# Micro.net
KiCad netlist of a schematic drawn in Altium Designer
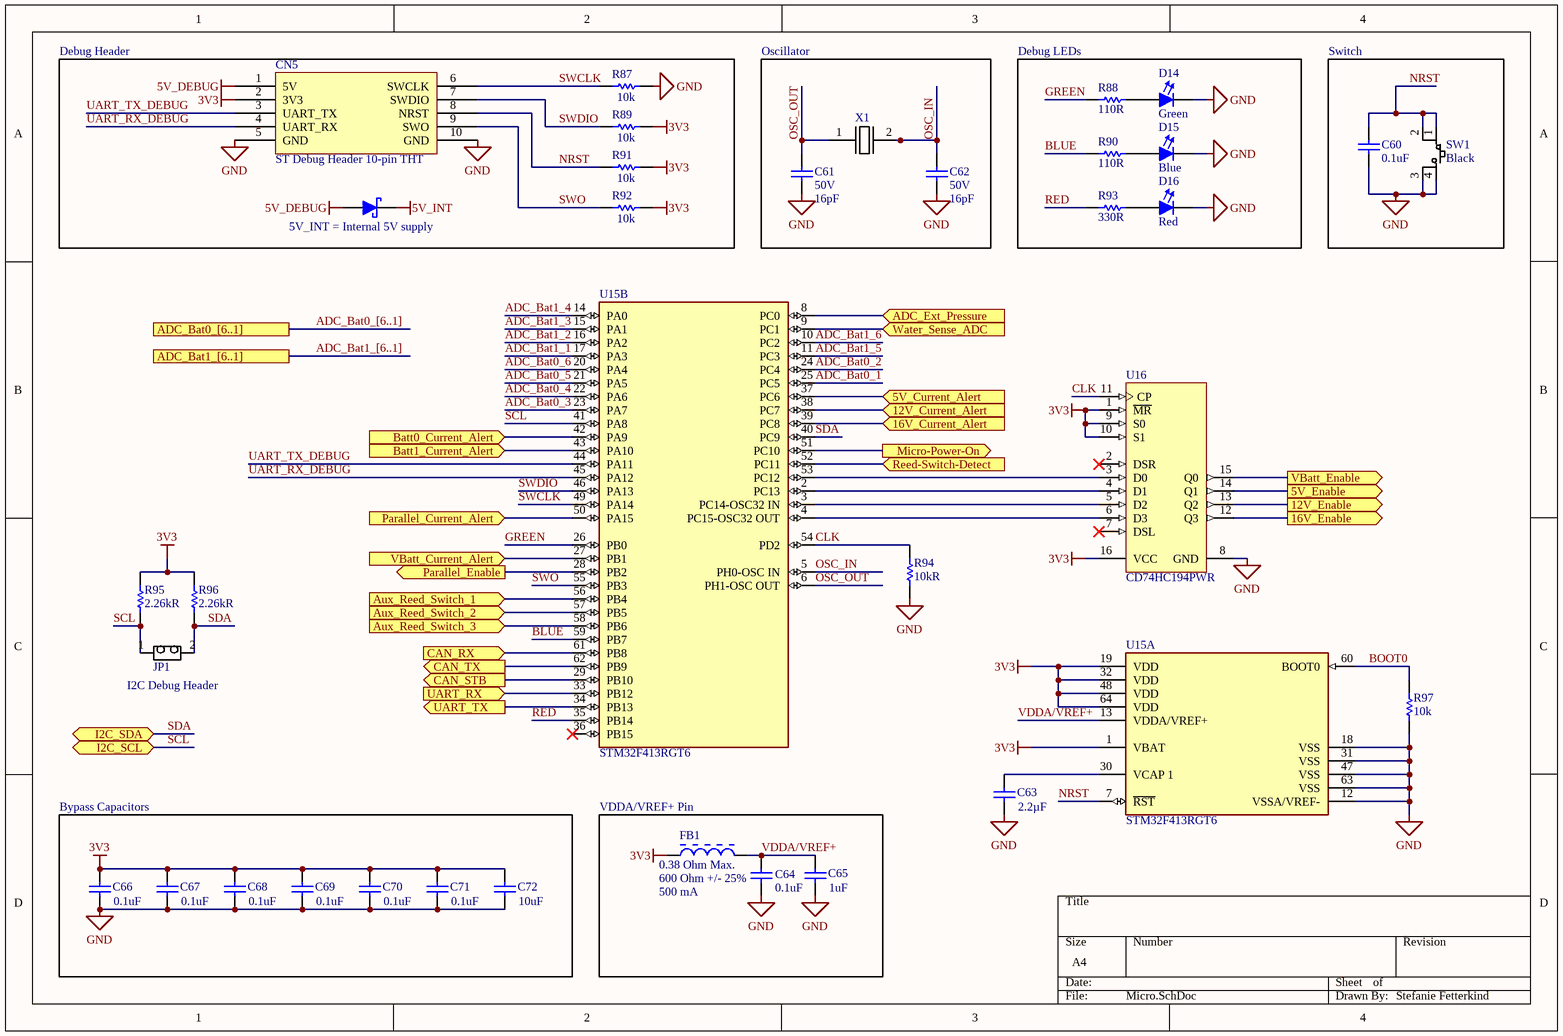
[diagram p0: Micro.SchDoc]

(export (version "E")
  (design (tool "Eeschema 10.0.6"))
  (components
    (comp (ref "C60")
      (value "CL10B104JB8NNNC")
      (footprint "FP-CL10-0_1-IPC_A")
      (description "CAP CER 0.1UF 50V X7R 0603")
      (fields
        (field (name "TOLERANCE") "5%")
        (field (name "VOLTAGE") "50V")
        (field (name "CAPACITANCE") "0.1uF")
      )
      (libsource (lib "AUVIC") (part "CAP-NP-2"))
    )
    (comp (ref "C61")
      (value "16pF Ceramic 50V 5% 0603")
      (footprint "CAPC1608X90X35LL10T15")
      (description "Cap Ceramic 16pF 50V C0G 5% SMD 0603 125C Paper T/R")
      (fields
        (field (name "VOLTAGE") "50V")
        (field (name "TOLERANCE") "5%")
        (field (name "CAPACITANCE") "16pF")
      )
      (libsource (lib "AUVIC") (part "CAP"))
    )
    (comp (ref "C62")
      (value "16pF Ceramic 50V 5% 0603")
      (footprint "CAPC1608X90X35LL10T15")
      (description "Cap Ceramic 16pF 50V C0G 5% SMD 0603 125C Paper T/R")
      (fields
        (field (name "VOLTAGE") "50V")
        (field (name "TOLERANCE") "5%")
        (field (name "CAPACITANCE") "16pF")
      )
      (libsource (lib "AUVIC") (part "CAP"))
    )
    (comp (ref "C63")
      (value "2.2µF")
      (footprint "CAPC1608N(0603\")")
      (description "Capacitor, Ceramic, 50V, 10%, 0603 SMD, X5R")
      (fields
        (field (name "Comment") "2.2uF, 50V, 0603 SMD, X5R, Ceramic")
        (field (name "MADE BY") "*")
        (field (name "PUBLISHER") "AUVic")
      )
      (libsource (lib "AUVIC") (part "Symbol"))
    )
    (comp (ref "C64")
      (value "CL10B104JB8NNNC")
      (footprint "FP-CL10-0_1-IPC_A")
      (description "CAP CER 0.1UF 50V X7R 0603")
      (fields
        (field (name "CAPACITANCE") "0.1uF")
        (field (name "VOLTAGE") "50V")
        (field (name "TOLERANCE") "5%")
      )
      (libsource (lib "AUVIC") (part "CAP-NP-2"))
    )
    (comp (ref "C65")
      (value "CL21B105KBFNNNG")
      (footprint "0803 CAP")
      (description "SAMSUNG ELECTRO-MECHANICS - CL21B105KBFNNNG - MLCC CAPACITORS")
      (fields
        (field (name "TOLERANCE") "10%")
        (field (name "CAPACITANCE") "1uF")
        (field (name "VOLTAGE") "50V")
      )
      (libsource (lib "") (part "Symbol_1"))
    )
    (comp (ref "C66")
      (value "CL10B104JB8NNNC")
      (footprint "FP-CL10-0_1-IPC_A")
      (description "CAP CER 0.1UF 50V X7R 0603")
      (fields
        (field (name "CAPACITANCE") "0.1uF")
        (field (name "VOLTAGE") "50V")
        (field (name "TOLERANCE") "5%")
      )
      (libsource (lib "AUVIC") (part "CAP-NP-2"))
    )
    (comp (ref "C67")
      (value "CL10B104JB8NNNC")
      (footprint "FP-CL10-0_1-IPC_A")
      (description "CAP CER 0.1UF 50V X7R 0603")
      (fields
        (field (name "CAPACITANCE") "0.1uF")
        (field (name "VOLTAGE") "50V")
        (field (name "TOLERANCE") "5%")
      )
      (libsource (lib "AUVIC") (part "CAP-NP-2"))
    )
    (comp (ref "C68")
      (value "CL10B104JB8NNNC")
      (footprint "FP-CL10-0_1-IPC_A")
      (description "CAP CER 0.1UF 50V X7R 0603")
      (fields
        (field (name "CAPACITANCE") "0.1uF")
        (field (name "VOLTAGE") "50V")
        (field (name "TOLERANCE") "5%")
      )
      (libsource (lib "AUVIC") (part "CAP-NP-2"))
    )
    (comp (ref "C69")
      (value "CL10B104JB8NNNC")
      (footprint "FP-CL10-0_1-IPC_A")
      (description "CAP CER 0.1UF 50V X7R 0603")
      (fields
        (field (name "CAPACITANCE") "0.1uF")
        (field (name "VOLTAGE") "50V")
        (field (name "TOLERANCE") "5%")
      )
      (libsource (lib "AUVIC") (part "CAP-NP-2"))
    )
    (comp (ref "C70")
      (value "CL10B104JB8NNNC")
      (footprint "FP-CL10-0_1-IPC_A")
      (description "CAP CER 0.1UF 50V X7R 0603")
      (fields
        (field (name "CAPACITANCE") "0.1uF")
        (field (name "VOLTAGE") "50V")
        (field (name "TOLERANCE") "5%")
      )
      (libsource (lib "AUVIC") (part "CAP-NP-2"))
    )
    (comp (ref "C71")
      (value "CL10B104JB8NNNC")
      (footprint "FP-CL10-0_1-IPC_A")
      (description "CAP CER 0.1UF 50V X7R 0603")
      (fields
        (field (name "CAPACITANCE") "0.1uF")
        (field (name "VOLTAGE") "50V")
        (field (name "TOLERANCE") "5%")
      )
      (libsource (lib "AUVIC") (part "CAP-NP-2"))
    )
    (comp (ref "C72")
      (value "CL31B106KBHNNNE")
      (footprint "CAPC3216X180X50ML20T30")
      (description "Cap Ceramic 10uF 50V X7R 10% Pad SMD 1206 125°C T/R")
      (fields (field (name "CAPACITANCE") "10uF") (field (name "TOLERANCE") "10%"))
      (libsource (lib "AUVIC") (part "CAP-NP-2"))
    )
    (comp (ref "CN5")
      (value "ST Debug Header 10-pin THT")
      (footprint "10-pin shrouded header THT")
      (description "CONN HEADER VERT 10POS 2.54MM")
      (libsource (lib "AUVIC") (part "ST Debug Header 10-pin"))
    )
    (comp (ref "D14")
      (value "LT Q39G-Q1OO-25-1")
      (footprint "FP-LB_Q39E-MFG")
      (description "LED GREEN DIFFUSED 0603 SMD")
      (fields (field (name "COLOR") "Green"))
      (libsource (lib "") (part "Symbol_3"))
    )
    (comp (ref "D15")
      (value "LBQ39E-N1OO-35-1")
      (footprint "FP-LB_Q39E-MFG")
      (description "LED BLUE DIFFUSED 0603 SMD")
      (fields (field (name "COLOR") "Blue"))
      (libsource (lib "") (part "Symbol_3"))
    )
    (comp (ref "D16")
      (value "LSQ976-NR-1")
      (footprint "FP-LB_Q39E-MFG")
      (description "LED Red 645nm 2-Pin Chip 0603(1608Metric) T/R")
      (fields (field (name "COLOR") "Red"))
      (libsource (lib "") (part "Symbol_3"))
    )
    (comp (ref "D17")
      (value "CUS08F30,H3F")
      (footprint "SC-76")
      (description "Diode Schottky 30V 800mA Surface Mount USC")
      (libsource (lib "") (part "Symbol_5"))
    )
    (comp (ref "FB1")
      (value "BLM18AG601SN1D")
      (footprint "MURA-BLM18-F-H1-CHIP-2_V")
      (fields
        (field (name "MANUFACTURER") "Murata")
        (field (name "DC RESISTANCE") "0.38 Ohm Max.")
        (field (name "IMPEDANCE (AT 100 MHZ)") "600 Ohm +/- 25%")
        (field (name "RATED CURRENT") "500 mA")
      )
      (libsource (lib "Altium Content Vault") (part "MURA-FB-2"))
    )
    (comp (ref "JP1")
      (value "1x2 Male Header")
      (footprint "2X1 Males Header")
      (fields (field (name "MADE BY") "Andy Bates"))
      (libsource (lib "AUVIC") (part "1x2 Male Header"))
    )
    (comp (ref "R87")
      (value "10k")
      (footprint "RESC1608N(0603\")")
      (description "10kR, 1%, 1/10W, 0603 SMD")
      (fields (field (name "MADE BY") "Ashwin Sira"))
      (libsource (lib "") (part "Symbol_4"))
    )
    (comp (ref "R88")
      (value "RC0603FR-07110RL")
      (footprint "RESC1608X55X25ML10T15")
      (description "RES SMD 110 OHM 1% 1/10W 0603")
      (fields (field (name "TOLERANCE") "1%") (field (name "RESISTANCE") "110R"))
      (libsource (lib "AUVIC") (part "RES"))
    )
    (comp (ref "R89")
      (value "10k")
      (footprint "RESC1608N(0603\")")
      (description "10kR, 1%, 1/10W, 0603 SMD")
      (fields (field (name "MADE BY") "Ashwin Sira"))
      (libsource (lib "") (part "Symbol_4"))
    )
    (comp (ref "R90")
      (value "RC0603FR-07110RL")
      (footprint "RESC1608X55X25ML10T15")
      (description "RES SMD 110 OHM 1% 1/10W 0603")
      (fields (field (name "TOLERANCE") "1%") (field (name "RESISTANCE") "110R"))
      (libsource (lib "AUVIC") (part "RES"))
    )
    (comp (ref "R91")
      (value "10k")
      (footprint "RESC1608N(0603\")")
      (description "10kR, 1%, 1/10W, 0603 SMD")
      (fields (field (name "MADE BY") "Ashwin Sira"))
      (libsource (lib "") (part "Symbol_4"))
    )
    (comp (ref "R92")
      (value "10k")
      (footprint "RESC1608N(0603\")")
      (description "10kR, 1%, 1/10W, 0603 SMD")
      (fields (field (name "MADE BY") "Ashwin Sira"))
      (libsource (lib "") (part "Symbol_4"))
    )
    (comp (ref "R93")
      (value "CRCW0603330RFKEA")
      (footprint "FP-CRCW0603-e3-IPC_A")
      (description "Res Thick Film 0603 330 Ohm 1% 0.1W(1/10W) +/-100ppm/ßC Pad SMD Automotive T/R")
      (fields (field (name "RESISTANCE") "330R") (field (name "TOLERANCE") "1%"))
      (libsource (lib "AUVIC") (part "RES"))
    )
    (comp (ref "R94")
      (value "RC0603FR-0710KL")
      (footprint "RESC1608X55X25ML10T15")
      (description "Res General Purpose Thick Film 0603 10K Ohm 1% 1/10W ±100ppm/°C Molded SMD Paper T/R")
      (fields (field (name "RESISTANCE") "10kR") (field (name "TOLERANCE") "1%"))
      (libsource (lib "AUVIC") (part "RES-2"))
    )
    (comp (ref "R95")
      (value "RC0603FR-072K26L")
      (footprint "RESC0603(1608)_M")
      (description "RES SMD 2.26K OHM 1% 1/10W 0603")
      (fields (field (name "TOLERANCE") "1%") (field (name "RESISTANCE") "2.26kR"))
      (libsource (lib "AUVIC") (part "RES"))
    )
    (comp (ref "R96")
      (value "RC0603FR-072K26L")
      (footprint "RESC0603(1608)_M")
      (description "RES SMD 2.26K OHM 1% 1/10W 0603")
      (fields (field (name "TOLERANCE") "1%") (field (name "RESISTANCE") "2.26kR"))
      (libsource (lib "AUVIC") (part "RES"))
    )
    (comp (ref "R97")
      (value "10k")
      (footprint "RESC1608N(0603\")")
      (description "10kR, 1%, 1/10W, 0603 SMD")
      (fields (field (name "MADE BY") "Ashwin Sira"))
      (libsource (lib "") (part "Symbol_4"))
    )
    (comp (ref "SW1")
      (value "PTS645SL43SMTR92LFS")
      (footprint "4-SPST-NO")
      (description "Black Switch Tactile N.O. SPST Round Button Gull Wing 0.05A 12VDC 100000Cycles 1.27N SMD T/R")
      (fields (field (name "BUTTON COLOUR") "Black"))
      (libsource (lib "") (part "Symbol_6"))
    )
    (comp (ref "U15")
      (value "STM32F413RGT6")
      (footprint "FP-LQFP64-5W-IPC_A")
      (description "STMICROELECTRONICS - STM32F413RGT6 - MCU, ARM CORTEX-M4, 100MHZ, LQFP-64")
      (libsource (lib "AUVIC") (part "7f3deadac312a1e532344b4e443717e"))
    )
    (comp (ref "U16")
      (value "CD74HC194PWR")
      (footprint "PW0016A_M")
      (description "IC SHFT REGSTR UNIV BIDIR16TSSOP")
      (libsource (lib "AUVIC") (part "TI-CD74HCX194-16"))
    )
    (comp (ref "X1")
      (value "Oscillator 8MHz 40ESR")
      (footprint "HC49/US")
      (description "8Mhz 40ESR  16pF -20°C ~ 70°C")
      (fields (field (name "MADE BY") "Lyden Smith"))
      (libsource (lib "") (part "Symbol_2"))
    )
  )
  (nets
    (net (code "1") (name "/5V_Current_Alert") (class "Default")
      (node (ref "U15") (pin "37") (pinfunction "PC6_37") (pintype "bidirectional"))
    )
    (net (code "2") (name "/5V_Enable") (class "Default")
      (node (ref "U16") (pin "14") (pinfunction "Q1_14") (pintype "output"))
    )
    (net (code "3") (name "/12V_Current_Alert") (class "Default")
      (node (ref "U15") (pin "38") (pinfunction "PC7_38") (pintype "bidirectional"))
    )
    (net (code "4") (name "/12V_Enable") (class "Default")
      (node (ref "U16") (pin "13") (pinfunction "Q2_13") (pintype "output"))
    )
    (net (code "5") (name "/16V_Current_Alert") (class "Default")
      (node (ref "U15") (pin "39") (pinfunction "PC8_39") (pintype "bidirectional"))
    )
    (net (code "6") (name "/16V_Enable") (class "Default")
      (node (ref "U16") (pin "12") (pinfunction "Q3_12") (pintype "output"))
    )
    (net (code "7") (name "/ADC_Bat0_1") (class "Default")
      (node (ref "U15") (pin "25") (pinfunction "PC5_25") (pintype "bidirectional"))
    )
    (net (code "8") (name "/ADC_Bat0_2") (class "Default")
      (node (ref "U15") (pin "24") (pinfunction "PC4_24") (pintype "bidirectional"))
    )
    (net (code "9") (name "/ADC_Bat0_3") (class "Default")
      (node (ref "U15") (pin "23") (pinfunction "PA7_23") (pintype "bidirectional"))
    )
    (net (code "10") (name "/ADC_Bat0_4") (class "Default")
      (node (ref "U15") (pin "22") (pinfunction "PA6_22") (pintype "bidirectional"))
    )
    (net (code "11") (name "/ADC_Bat0_5") (class "Default")
      (node (ref "U15") (pin "21") (pinfunction "PA5_21") (pintype "bidirectional"))
    )
    (net (code "12") (name "/ADC_Bat0_6") (class "Default")
      (node (ref "U15") (pin "20") (pinfunction "PA4_20") (pintype "bidirectional"))
    )
    (net (code "14") (name "/ADC_Bat1_1") (class "Default")
      (node (ref "U15") (pin "17") (pinfunction "PA3_17") (pintype "bidirectional"))
    )
    (net (code "15") (name "/ADC_Bat1_2") (class "Default")
      (node (ref "U15") (pin "16") (pinfunction "PA2_16") (pintype "bidirectional"))
    )
    (net (code "16") (name "/ADC_Bat1_3") (class "Default")
      (node (ref "U15") (pin "15") (pinfunction "PA1_15") (pintype "bidirectional"))
    )
    (net (code "17") (name "/ADC_Bat1_4") (class "Default")
      (node (ref "U15") (pin "14") (pinfunction "PA0_14") (pintype "bidirectional"))
    )
    (net (code "18") (name "/ADC_Bat1_5") (class "Default")
      (node (ref "U15") (pin "11") (pinfunction "PC3_11") (pintype "bidirectional"))
    )
    (net (code "19") (name "/ADC_Bat1_6") (class "Default")
      (node (ref "U15") (pin "10") (pinfunction "PC2_10") (pintype "bidirectional"))
    )
    (net (code "21") (name "/ADC_Ext_Pressure") (class "Default")
      (node (ref "U15") (pin "8") (pinfunction "PC0_8") (pintype "bidirectional"))
    )
    (net (code "22") (name "/Aux_Reed_Switch_1") (class "Default")
      (node (ref "U15") (pin "56") (pinfunction "PB4_56") (pintype "bidirectional"))
    )
    (net (code "23") (name "/Aux_Reed_Switch_2") (class "Default")
      (node (ref "U15") (pin "57") (pinfunction "PB5_57") (pintype "bidirectional"))
    )
    (net (code "24") (name "/Aux_Reed_Switch_3") (class "Default")
      (node (ref "U15") (pin "58") (pinfunction "PB6_58") (pintype "bidirectional"))
    )
    (net (code "25") (name "/BLUE") (class "Default")
      (node (ref "R90") (pin "2") (pinfunction "2_2") (pintype "passive"))
      (node (ref "U15") (pin "59") (pinfunction "PB7_59") (pintype "bidirectional"))
    )
    (net (code "26") (name "/BOOT0") (class "Default")
      (node (ref "R97") (pin "2") (pinfunction "2_2") (pintype "passive"))
      (node (ref "U15") (pin "60") (pinfunction "BOOT0_60") (pintype "input"))
    )
    (net (code "27") (name "/Batt0_Current_Alert") (class "Default")
      (node (ref "U15") (pin "42") (pinfunction "PA9_42") (pintype "bidirectional"))
    )
    (net (code "28") (name "/Batt1_Current_Alert") (class "Default")
      (node (ref "U15") (pin "43") (pinfunction "PA10_43") (pintype "bidirectional"))
    )
    (net (code "29") (name "/CAN_RX") (class "Default")
      (node (ref "U15") (pin "61") (pinfunction "PB8_61") (pintype "bidirectional"))
    )
    (net (code "30") (name "/CAN_STB") (class "Default")
      (node (ref "U15") (pin "29") (pinfunction "PB10_29") (pintype "bidirectional"))
    )
    (net (code "31") (name "/CAN_TX") (class "Default")
      (node (ref "U15") (pin "62") (pinfunction "PB9_62") (pintype "bidirectional"))
    )
    (net (code "32") (name "/CLK") (class "Default")
      (node (ref "R94") (pin "1") (pinfunction "1_1") (pintype "passive"))
      (node (ref "U15") (pin "54") (pinfunction "PD2_54") (pintype "bidirectional"))
      (node (ref "U16") (pin "11") (pinfunction "CP_11") (pintype "input"))
    )
    (net (code "33") (name "/GREEN") (class "Default")
      (node (ref "R88") (pin "2") (pinfunction "2_2") (pintype "passive"))
      (node (ref "U15") (pin "26") (pinfunction "PB0_26") (pintype "bidirectional"))
    )
    (net (code "34") (name "/Micro-Power-On") (class "Default")
      (node (ref "U15") (pin "51") (pinfunction "PC10_51") (pintype "bidirectional"))
    )
    (net (code "35") (name "/NRST") (class "Default")
      (node (ref "C60") (pin "1") (pinfunction "1_1") (pintype "passive"))
      (node (ref "CN5") (pin "8") (pinfunction "NRST_8") (pintype "passive"))
      (node (ref "R91") (pin "1") (pinfunction "1_1") (pintype "passive"))
      (node (ref "SW1") (pin "1") (pinfunction "1_1") (pintype "passive"))
      (node (ref "SW1") (pin "2") (pinfunction "2_2") (pintype "passive"))
      (node (ref "U15") (pin "7") (pinfunction "~{RST}_7") (pintype "bidirectional"))
    )
    (net (code "36") (name "/OSC_IN") (class "Default")
      (node (ref "C62") (pin "2") (pinfunction "2_2") (pintype "passive"))
      (node (ref "U15") (pin "5") (pinfunction "PH0-OSC_IN_5") (pintype "bidirectional"))
      (node (ref "X1") (pin "2") (pinfunction "2_2") (pintype "passive"))
    )
    (net (code "37") (name "/OSC_OUT") (class "Default")
      (node (ref "C61") (pin "2") (pinfunction "2_2") (pintype "passive"))
      (node (ref "U15") (pin "6") (pinfunction "PH1-OSC_OUT_6") (pintype "bidirectional"))
      (node (ref "X1") (pin "1") (pinfunction "1_1") (pintype "passive"))
    )
    (net (code "38") (name "/Parallel_Current_Alert") (class "Default")
      (node (ref "U15") (pin "50") (pinfunction "PA15_50") (pintype "bidirectional"))
    )
    (net (code "39") (name "/Parallel_Enable") (class "Default")
      (node (ref "U15") (pin "28") (pinfunction "PB2_28") (pintype "bidirectional"))
    )
    (net (code "40") (name "/RED") (class "Default")
      (node (ref "R93") (pin "1") (pinfunction "1_1") (pintype "passive"))
      (node (ref "U15") (pin "35") (pinfunction "PB14_35") (pintype "bidirectional"))
    )
    (net (code "41") (name "/Reed-Switch-Detect") (class "Default")
      (node (ref "U15") (pin "52") (pinfunction "PC11_52") (pintype "bidirectional"))
    )
    (net (code "42") (name "/SCL") (class "Default")
      (node (ref "JP1") (pin "1") (pinfunction "1_1") (pintype "passive"))
      (node (ref "R95") (pin "1") (pinfunction "1_1") (pintype "passive"))
      (node (ref "U15") (pin "41") (pinfunction "PA8_41") (pintype "bidirectional"))
    )
    (net (code "43") (name "/SDA") (class "Default")
      (node (ref "JP1") (pin "2") (pinfunction "2_2") (pintype "passive"))
      (node (ref "R96") (pin "1") (pinfunction "1_1") (pintype "passive"))
      (node (ref "U15") (pin "40") (pinfunction "PC9_40") (pintype "bidirectional"))
    )
    (net (code "44") (name "/SWCLK") (class "Default")
      (node (ref "CN5") (pin "6") (pinfunction "SWCLK_6") (pintype "passive"))
      (node (ref "R87") (pin "1") (pinfunction "1_1") (pintype "passive"))
      (node (ref "U15") (pin "49") (pinfunction "PA14_49") (pintype "bidirectional"))
    )
    (net (code "45") (name "/SWDIO") (class "Default")
      (node (ref "CN5") (pin "7") (pinfunction "SWDIO_7") (pintype "passive"))
      (node (ref "R89") (pin "1") (pinfunction "1_1") (pintype "passive"))
      (node (ref "U15") (pin "46") (pinfunction "PA13_46") (pintype "bidirectional"))
    )
    (net (code "46") (name "/SWO") (class "Default")
      (node (ref "CN5") (pin "9") (pinfunction "SWO_9") (pintype "passive"))
      (node (ref "R92") (pin "1") (pinfunction "1_1") (pintype "passive"))
      (node (ref "U15") (pin "55") (pinfunction "PB3_55") (pintype "bidirectional"))
    )
    (net (code "47") (name "/UART_RX") (class "Default")
      (node (ref "U15") (pin "33") (pinfunction "PB12_33") (pintype "bidirectional"))
    )
    (net (code "48") (name "/UART_RX_DEBUG") (class "Default")
      (node (ref "CN5") (pin "4") (pinfunction "UART_RX_4") (pintype "passive"))
      (node (ref "U15") (pin "45") (pinfunction "PA12_45") (pintype "bidirectional"))
    )
    (net (code "49") (name "/UART_TX") (class "Default")
      (node (ref "U15") (pin "34") (pinfunction "PB13_34") (pintype "bidirectional"))
    )
    (net (code "50") (name "/UART_TX_DEBUG") (class "Default")
      (node (ref "CN5") (pin "3") (pinfunction "UART_TX_3") (pintype "passive"))
      (node (ref "U15") (pin "44") (pinfunction "PA11_44") (pintype "bidirectional"))
    )
    (net (code "51") (name "/VBatt_Current_Alert") (class "Default")
      (node (ref "U15") (pin "27") (pinfunction "PB1_27") (pintype "bidirectional"))
    )
    (net (code "52") (name "/VBatt_Enable") (class "Default")
      (node (ref "U16") (pin "15") (pinfunction "Q0_15") (pintype "output"))
    )
    (net (code "53") (name "/VDDA{slash}VREF+") (class "Default")
      (node (ref "C64") (pin "1") (pinfunction "1_1") (pintype "passive"))
      (node (ref "C65") (pin "2") (pinfunction "2_2") (pintype "passive"))
      (node (ref "FB1") (pin "2") (pinfunction "2_2") (pintype "passive"))
      (node (ref "U15") (pin "13") (pinfunction "VDDA/VREF+_13") (pintype "power_in"))
    )
    (net (code "54") (name "/Water_Sense_ADC") (class "Default")
      (node (ref "U15") (pin "9") (pinfunction "PC1_9") (pintype "bidirectional"))
    )
    (net (code "55") (name "3V3") (class "Default")
      (node (ref "C66") (pin "1") (pinfunction "1_1") (pintype "passive"))
      (node (ref "C67") (pin "1") (pinfunction "1_1") (pintype "passive"))
      (node (ref "C68") (pin "1") (pinfunction "1_1") (pintype "passive"))
      (node (ref "C69") (pin "1") (pinfunction "1_1") (pintype "passive"))
      (node (ref "C70") (pin "1") (pinfunction "1_1") (pintype "passive"))
      (node (ref "C71") (pin "1") (pinfunction "1_1") (pintype "passive"))
      (node (ref "C72") (pin "2") (pinfunction "2_2") (pintype "passive"))
      (node (ref "CN5") (pin "2") (pinfunction "3V3_2") (pintype "passive"))
      (node (ref "FB1") (pin "1") (pinfunction "1_1") (pintype "passive"))
      (node (ref "R89") (pin "2") (pinfunction "2_2") (pintype "passive"))
      (node (ref "R91") (pin "2") (pinfunction "2_2") (pintype "passive"))
      (node (ref "R92") (pin "2") (pinfunction "2_2") (pintype "passive"))
      (node (ref "R95") (pin "2") (pinfunction "2_2") (pintype "passive"))
      (node (ref "R96") (pin "2") (pinfunction "2_2") (pintype "passive"))
      (node (ref "U15") (pin "1") (pinfunction "VBAT_1") (pintype "power_in"))
      (node (ref "U15") (pin "19") (pinfunction "VDD_19") (pintype "power_in"))
      (node (ref "U15") (pin "32") (pinfunction "VDD_32") (pintype "power_in"))
      (node (ref "U15") (pin "48") (pinfunction "VDD_48") (pintype "power_in"))
      (node (ref "U15") (pin "64") (pinfunction "VDD_64") (pintype "power_in"))
      (node (ref "U16") (pin "1") (pinfunction "~{MR}_1") (pintype "input"))
      (node (ref "U16") (pin "10") (pinfunction "S1_10") (pintype "input"))
      (node (ref "U16") (pin "16") (pinfunction "VCC_16") (pintype "power_in"))
      (node (ref "U16") (pin "9") (pinfunction "S0_9") (pintype "input"))
    )
    (net (code "56") (name "5V_DEBUG") (class "Default")
      (node (ref "CN5") (pin "1") (pinfunction "5V_1") (pintype "passive"))
      (node (ref "D17") (pin "A") (pinfunction "Anode_A") (pintype "passive"))
    )
    (net (code "57") (name "5V_INT") (class "Default")
      (node (ref "D17") (pin "K") (pinfunction "Cathode_K") (pintype "passive"))
    )
    (net (code "58") (name "GND") (class "Default")
      (node (ref "C60") (pin "2") (pinfunction "2_2") (pintype "passive"))
      (node (ref "C61") (pin "1") (pinfunction "1_1") (pintype "passive"))
      (node (ref "C62") (pin "1") (pinfunction "1_1") (pintype "passive"))
      (node (ref "C63") (pin "1") (pinfunction "Anode_1") (pintype "passive"))
      (node (ref "C64") (pin "2") (pinfunction "2_2") (pintype "passive"))
      (node (ref "C65") (pin "1") (pinfunction "1_1") (pintype "passive"))
      (node (ref "C66") (pin "2") (pinfunction "2_2") (pintype "passive"))
      (node (ref "C67") (pin "2") (pinfunction "2_2") (pintype "passive"))
      (node (ref "C68") (pin "2") (pinfunction "2_2") (pintype "passive"))
      (node (ref "C69") (pin "2") (pinfunction "2_2") (pintype "passive"))
      (node (ref "C70") (pin "2") (pinfunction "2_2") (pintype "passive"))
      (node (ref "C71") (pin "2") (pinfunction "2_2") (pintype "passive"))
      (node (ref "C72") (pin "1") (pinfunction "1_1") (pintype "passive"))
      (node (ref "CN5") (pin "10") (pinfunction "GND_10") (pintype "passive"))
      (node (ref "CN5") (pin "5") (pinfunction "GND_5") (pintype "passive"))
      (node (ref "D14") (pin "1") (pinfunction "Cathode_1") (pintype "passive"))
      (node (ref "D15") (pin "1") (pinfunction "Cathode_1") (pintype "passive"))
      (node (ref "D16") (pin "1") (pinfunction "Cathode_1") (pintype "passive"))
      (node (ref "R87") (pin "2") (pinfunction "2_2") (pintype "passive"))
      (node (ref "R94") (pin "2") (pinfunction "2_2") (pintype "passive"))
      (node (ref "R97") (pin "1") (pinfunction "1_1") (pintype "passive"))
      (node (ref "SW1") (pin "3") (pinfunction "3_3") (pintype "passive"))
      (node (ref "SW1") (pin "4") (pinfunction "4_4") (pintype "passive"))
      (node (ref "U15") (pin "12") (pinfunction "VSSA/VREF-_12") (pintype "power_in"))
      (node (ref "U15") (pin "18") (pinfunction "VSS_18") (pintype "power_in"))
      (node (ref "U15") (pin "31") (pinfunction "VSS_31") (pintype "power_in"))
      (node (ref "U15") (pin "47") (pinfunction "VSS_47") (pintype "power_in"))
      (node (ref "U15") (pin "63") (pinfunction "VSS_63") (pintype "power_in"))
      (node (ref "U16") (pin "8") (pinfunction "GND_8") (pintype "power_in"))
    )
    (net (code "59") (name "Net-(C63-Cathode)") (class "Default")
      (node (ref "C63") (pin "2") (pinfunction "Cathode_2") (pintype "passive"))
      (node (ref "U15") (pin "30") (pinfunction "VCAP_1_30") (pintype "power_in"))
    )
    (net (code "60") (name "Net-(D14-Anode)") (class "Default")
      (node (ref "D14") (pin "2") (pinfunction "Anode_2") (pintype "passive"))
      (node (ref "R88") (pin "1") (pinfunction "1_1") (pintype "passive"))
    )
    (net (code "61") (name "Net-(D15-Anode)") (class "Default")
      (node (ref "D15") (pin "2") (pinfunction "Anode_2") (pintype "passive"))
      (node (ref "R90") (pin "1") (pinfunction "1_1") (pintype "passive"))
    )
    (net (code "62") (name "Net-(D16-Anode)") (class "Default")
      (node (ref "D16") (pin "2") (pinfunction "Anode_2") (pintype "passive"))
      (node (ref "R93") (pin "2") (pinfunction "2_2") (pintype "passive"))
    )
    (net (code "63") (name "Net-(U15B-PC12)") (class "Default")
      (node (ref "U15") (pin "53") (pinfunction "PC12_53") (pintype "bidirectional"))
      (node (ref "U16") (pin "3") (pinfunction "D0_3") (pintype "input"))
    )
    (net (code "64") (name "Net-(U15B-PC13)") (class "Default")
      (node (ref "U15") (pin "2") (pinfunction "PC13_2") (pintype "bidirectional"))
      (node (ref "U16") (pin "4") (pinfunction "D1_4") (pintype "input"))
    )
    (net (code "65") (name "Net-(U15B-PC14-OSC32_IN)") (class "Default")
      (node (ref "U15") (pin "3") (pinfunction "PC14-OSC32_IN_3") (pintype "bidirectional"))
      (node (ref "U16") (pin "5") (pinfunction "D2_5") (pintype "input"))
    )
    (net (code "66") (name "Net-(U15B-PC15-OSC32_OUT)") (class "Default")
      (node (ref "U15") (pin "4") (pinfunction "PC15-OSC32_OUT_4") (pintype "bidirectional"))
      (node (ref "U16") (pin "6") (pinfunction "D3_6") (pintype "input"))
    )
    (net (code "67") (name "unconnected-(U15B-PB15-Pad36)") (class "Default")
      (node (ref "U15") (pin "36") (pinfunction "PB15_36") (pintype "bidirectional+no_connect"))
    )
    (net (code "68") (name "unconnected-(U16-DSL-Pad7)") (class "Default")
      (node (ref "U16") (pin "7") (pinfunction "DSL_7") (pintype "input+no_connect"))
    )
    (net (code "69") (name "unconnected-(U16-DSR-Pad2)") (class "Default")
      (node (ref "U16") (pin "2") (pinfunction "DSR_2") (pintype "input+no_connect"))
    )
  )
)
